# Others.net
KiCad netlist of a schematic drawn in Altium Designer
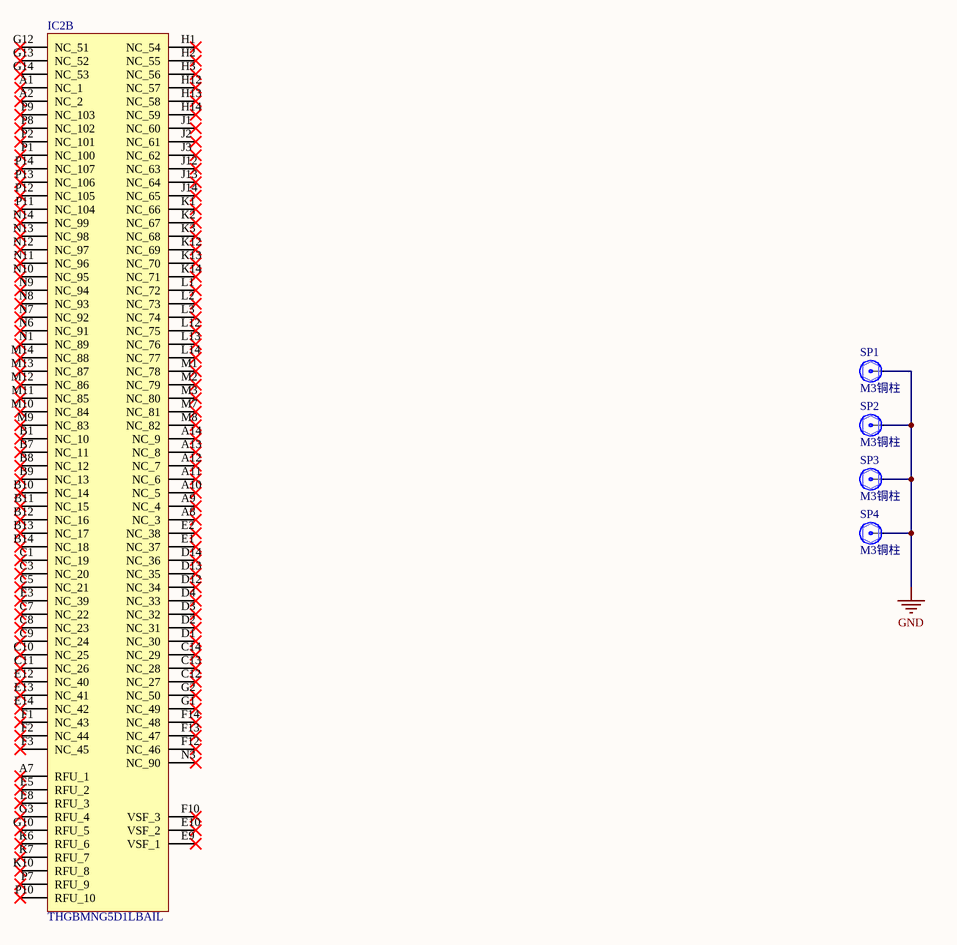
[diagram p0: Others.SchDoc]

(export (version "E")
  (design (tool "Eeschema 10.0.6"))
  (components
    (comp (ref "IC2")
      (value "THGBMNG5D1LBAIL")
      (footprint "SamacSys:BGA153C50P14X14_1150X1300X80")
      (description "Integrated Circuit")
      (libsource (lib "SamacSys") (part "THGBMNG5D1LBAIL"))
    )
    (comp (ref "SP1")
      (value "M3铜柱")
      (footprint "M3x4+6_L")
      (description "铜柱")
      (libsource (lib "0.5 - 按键_开关_蜂鸣器_电池_测试点_Mark点_铜柱") (part "铜柱加头小焊盘"))
    )
    (comp (ref "SP2")
      (value "M3铜柱")
      (footprint "M3x4+6_L")
      (description "铜柱")
      (libsource (lib "0.5 - 按键_开关_蜂鸣器_电池_测试点_Mark点_铜柱") (part "铜柱加头小焊盘"))
    )
    (comp (ref "SP3")
      (value "M3铜柱")
      (footprint "M3x4+6_L")
      (description "铜柱")
      (libsource (lib "0.5 - 按键_开关_蜂鸣器_电池_测试点_Mark点_铜柱") (part "铜柱加头小焊盘"))
    )
    (comp (ref "SP4")
      (value "M3铜柱")
      (footprint "M3x4+6_L")
      (description "铜柱")
      (libsource (lib "0.5 - 按键_开关_蜂鸣器_电池_测试点_Mark点_铜柱") (part "铜柱加头小焊盘"))
    )
  )
  (nets
    (net (code "1") (name "GND") (class "Default")
      (node (ref "SP1") (pin "1") (pinfunction "1_1") (pintype "passive"))
      (node (ref "SP2") (pin "1") (pinfunction "1_1") (pintype "passive"))
      (node (ref "SP3") (pin "1") (pinfunction "1_1") (pintype "passive"))
      (node (ref "SP4") (pin "1") (pinfunction "1_1") (pintype "passive"))
    )
    (net (code "2") (name "unconnected-(IC2B-NC_1-PadA1)") (class "Default")
      (node (ref "IC2") (pin "A1") (pinfunction "NC_1_A1") (pintype "passive+no_connect"))
    )
    (net (code "3") (name "unconnected-(IC2B-NC_2-PadA2)") (class "Default")
      (node (ref "IC2") (pin "A2") (pinfunction "NC_2_A2") (pintype "passive+no_connect"))
    )
    (net (code "4") (name "unconnected-(IC2B-NC_3-PadA8)") (class "Default")
      (node (ref "IC2") (pin "A8") (pinfunction "NC_3_A8") (pintype "passive+no_connect"))
    )
    (net (code "5") (name "unconnected-(IC2B-NC_4-PadA9)") (class "Default")
      (node (ref "IC2") (pin "A9") (pinfunction "NC_4_A9") (pintype "passive+no_connect"))
    )
    (net (code "6") (name "unconnected-(IC2B-NC_5-PadA10)") (class "Default")
      (node (ref "IC2") (pin "A10") (pinfunction "NC_5_A10") (pintype "passive+no_connect"))
    )
    (net (code "7") (name "unconnected-(IC2B-NC_6-PadA11)") (class "Default")
      (node (ref "IC2") (pin "A11") (pinfunction "NC_6_A11") (pintype "passive+no_connect"))
    )
    (net (code "8") (name "unconnected-(IC2B-NC_7-PadA12)") (class "Default")
      (node (ref "IC2") (pin "A12") (pinfunction "NC_7_A12") (pintype "passive+no_connect"))
    )
    (net (code "9") (name "unconnected-(IC2B-NC_8-PadA13)") (class "Default")
      (node (ref "IC2") (pin "A13") (pinfunction "NC_8_A13") (pintype "passive+no_connect"))
    )
    (net (code "10") (name "unconnected-(IC2B-NC_9-PadA14)") (class "Default")
      (node (ref "IC2") (pin "A14") (pinfunction "NC_9_A14") (pintype "passive+no_connect"))
    )
    (net (code "11") (name "unconnected-(IC2B-NC_10-PadB1)") (class "Default")
      (node (ref "IC2") (pin "B1") (pinfunction "NC_10_B1") (pintype "passive+no_connect"))
    )
    (net (code "12") (name "unconnected-(IC2B-NC_11-PadB7)") (class "Default")
      (node (ref "IC2") (pin "B7") (pinfunction "NC_11_B7") (pintype "passive+no_connect"))
    )
    (net (code "13") (name "unconnected-(IC2B-NC_12-PadB8)") (class "Default")
      (node (ref "IC2") (pin "B8") (pinfunction "NC_12_B8") (pintype "passive+no_connect"))
    )
    (net (code "14") (name "unconnected-(IC2B-NC_13-PadB9)") (class "Default")
      (node (ref "IC2") (pin "B9") (pinfunction "NC_13_B9") (pintype "passive+no_connect"))
    )
    (net (code "15") (name "unconnected-(IC2B-NC_14-PadB10)") (class "Default")
      (node (ref "IC2") (pin "B10") (pinfunction "NC_14_B10") (pintype "passive+no_connect"))
    )
    (net (code "16") (name "unconnected-(IC2B-NC_15-PadB11)") (class "Default")
      (node (ref "IC2") (pin "B11") (pinfunction "NC_15_B11") (pintype "passive+no_connect"))
    )
    (net (code "17") (name "unconnected-(IC2B-NC_16-PadB12)") (class "Default")
      (node (ref "IC2") (pin "B12") (pinfunction "NC_16_B12") (pintype "passive+no_connect"))
    )
    (net (code "18") (name "unconnected-(IC2B-NC_17-PadB13)") (class "Default")
      (node (ref "IC2") (pin "B13") (pinfunction "NC_17_B13") (pintype "passive+no_connect"))
    )
    (net (code "19") (name "unconnected-(IC2B-NC_18-PadB14)") (class "Default")
      (node (ref "IC2") (pin "B14") (pinfunction "NC_18_B14") (pintype "passive+no_connect"))
    )
    (net (code "20") (name "unconnected-(IC2B-NC_19-PadC1)") (class "Default")
      (node (ref "IC2") (pin "C1") (pinfunction "NC_19_C1") (pintype "passive+no_connect"))
    )
    (net (code "21") (name "unconnected-(IC2B-NC_20-PadC3)") (class "Default")
      (node (ref "IC2") (pin "C3") (pinfunction "NC_20_C3") (pintype "passive+no_connect"))
    )
    (net (code "22") (name "unconnected-(IC2B-NC_21-PadC5)") (class "Default")
      (node (ref "IC2") (pin "C5") (pinfunction "NC_21_C5") (pintype "passive+no_connect"))
    )
    (net (code "23") (name "unconnected-(IC2B-NC_22-PadC7)") (class "Default")
      (node (ref "IC2") (pin "C7") (pinfunction "NC_22_C7") (pintype "passive+no_connect"))
    )
    (net (code "24") (name "unconnected-(IC2B-NC_23-PadC8)") (class "Default")
      (node (ref "IC2") (pin "C8") (pinfunction "NC_23_C8") (pintype "passive+no_connect"))
    )
    (net (code "25") (name "unconnected-(IC2B-NC_24-PadC9)") (class "Default")
      (node (ref "IC2") (pin "C9") (pinfunction "NC_24_C9") (pintype "passive+no_connect"))
    )
    (net (code "26") (name "unconnected-(IC2B-NC_25-PadC10)") (class "Default")
      (node (ref "IC2") (pin "C10") (pinfunction "NC_25_C10") (pintype "passive+no_connect"))
    )
    (net (code "27") (name "unconnected-(IC2B-NC_26-PadC11)") (class "Default")
      (node (ref "IC2") (pin "C11") (pinfunction "NC_26_C11") (pintype "passive+no_connect"))
    )
    (net (code "28") (name "unconnected-(IC2B-NC_27-PadC12)") (class "Default")
      (node (ref "IC2") (pin "C12") (pinfunction "NC_27_C12") (pintype "passive+no_connect"))
    )
    (net (code "29") (name "unconnected-(IC2B-NC_28-PadC13)") (class "Default")
      (node (ref "IC2") (pin "C13") (pinfunction "NC_28_C13") (pintype "passive+no_connect"))
    )
    (net (code "30") (name "unconnected-(IC2B-NC_29-PadC14)") (class "Default")
      (node (ref "IC2") (pin "C14") (pinfunction "NC_29_C14") (pintype "passive+no_connect"))
    )
    (net (code "31") (name "unconnected-(IC2B-NC_30-PadD1)") (class "Default")
      (node (ref "IC2") (pin "D1") (pinfunction "NC_30_D1") (pintype "passive+no_connect"))
    )
    (net (code "32") (name "unconnected-(IC2B-NC_31-PadD2)") (class "Default")
      (node (ref "IC2") (pin "D2") (pinfunction "NC_31_D2") (pintype "passive+no_connect"))
    )
    (net (code "33") (name "unconnected-(IC2B-NC_32-PadD3)") (class "Default")
      (node (ref "IC2") (pin "D3") (pinfunction "NC_32_D3") (pintype "passive+no_connect"))
    )
    (net (code "34") (name "unconnected-(IC2B-NC_33-PadD4)") (class "Default")
      (node (ref "IC2") (pin "D4") (pinfunction "NC_33_D4") (pintype "passive+no_connect"))
    )
    (net (code "35") (name "unconnected-(IC2B-NC_34-PadD12)") (class "Default")
      (node (ref "IC2") (pin "D12") (pinfunction "NC_34_D12") (pintype "passive+no_connect"))
    )
    (net (code "36") (name "unconnected-(IC2B-NC_35-PadD13)") (class "Default")
      (node (ref "IC2") (pin "D13") (pinfunction "NC_35_D13") (pintype "passive+no_connect"))
    )
    (net (code "37") (name "unconnected-(IC2B-NC_36-PadD14)") (class "Default")
      (node (ref "IC2") (pin "D14") (pinfunction "NC_36_D14") (pintype "passive+no_connect"))
    )
    (net (code "38") (name "unconnected-(IC2B-NC_37-PadE1)") (class "Default")
      (node (ref "IC2") (pin "E1") (pinfunction "NC_37_E1") (pintype "passive+no_connect"))
    )
    (net (code "39") (name "unconnected-(IC2B-NC_38-PadE2)") (class "Default")
      (node (ref "IC2") (pin "E2") (pinfunction "NC_38_E2") (pintype "passive+no_connect"))
    )
    (net (code "40") (name "unconnected-(IC2B-NC_39-PadE3)") (class "Default")
      (node (ref "IC2") (pin "E3") (pinfunction "NC_39_E3") (pintype "passive+no_connect"))
    )
    (net (code "41") (name "unconnected-(IC2B-NC_40-PadE12)") (class "Default")
      (node (ref "IC2") (pin "E12") (pinfunction "NC_40_E12") (pintype "passive+no_connect"))
    )
    (net (code "42") (name "unconnected-(IC2B-NC_41-PadE13)") (class "Default")
      (node (ref "IC2") (pin "E13") (pinfunction "NC_41_E13") (pintype "passive+no_connect"))
    )
    (net (code "43") (name "unconnected-(IC2B-NC_42-PadE14)") (class "Default")
      (node (ref "IC2") (pin "E14") (pinfunction "NC_42_E14") (pintype "passive+no_connect"))
    )
    (net (code "44") (name "unconnected-(IC2B-NC_43-PadF1)") (class "Default")
      (node (ref "IC2") (pin "F1") (pinfunction "NC_43_F1") (pintype "passive+no_connect"))
    )
    (net (code "45") (name "unconnected-(IC2B-NC_44-PadF2)") (class "Default")
      (node (ref "IC2") (pin "F2") (pinfunction "NC_44_F2") (pintype "passive+no_connect"))
    )
    (net (code "46") (name "unconnected-(IC2B-NC_45-PadF3)") (class "Default")
      (node (ref "IC2") (pin "F3") (pinfunction "NC_45_F3") (pintype "passive+no_connect"))
    )
    (net (code "47") (name "unconnected-(IC2B-NC_46-PadF12)") (class "Default")
      (node (ref "IC2") (pin "F12") (pinfunction "NC_46_F12") (pintype "passive+no_connect"))
    )
    (net (code "48") (name "unconnected-(IC2B-NC_47-PadF13)") (class "Default")
      (node (ref "IC2") (pin "F13") (pinfunction "NC_47_F13") (pintype "passive+no_connect"))
    )
    (net (code "49") (name "unconnected-(IC2B-NC_48-PadF14)") (class "Default")
      (node (ref "IC2") (pin "F14") (pinfunction "NC_48_F14") (pintype "passive+no_connect"))
    )
    (net (code "50") (name "unconnected-(IC2B-NC_49-PadG1)") (class "Default")
      (node (ref "IC2") (pin "G1") (pinfunction "NC_49_G1") (pintype "passive+no_connect"))
    )
    (net (code "51") (name "unconnected-(IC2B-NC_50-PadG2)") (class "Default")
      (node (ref "IC2") (pin "G2") (pinfunction "NC_50_G2") (pintype "passive+no_connect"))
    )
    (net (code "52") (name "unconnected-(IC2B-NC_51-PadG12)") (class "Default")
      (node (ref "IC2") (pin "G12") (pinfunction "NC_51_G12") (pintype "passive+no_connect"))
    )
    (net (code "53") (name "unconnected-(IC2B-NC_52-PadG13)") (class "Default")
      (node (ref "IC2") (pin "G13") (pinfunction "NC_52_G13") (pintype "passive+no_connect"))
    )
    (net (code "54") (name "unconnected-(IC2B-NC_53-PadG14)") (class "Default")
      (node (ref "IC2") (pin "G14") (pinfunction "NC_53_G14") (pintype "passive+no_connect"))
    )
    (net (code "55") (name "unconnected-(IC2B-NC_54-PadH1)") (class "Default")
      (node (ref "IC2") (pin "H1") (pinfunction "NC_54_H1") (pintype "passive+no_connect"))
    )
    (net (code "56") (name "unconnected-(IC2B-NC_55-PadH2)") (class "Default")
      (node (ref "IC2") (pin "H2") (pinfunction "NC_55_H2") (pintype "passive+no_connect"))
    )
    (net (code "57") (name "unconnected-(IC2B-NC_56-PadH3)") (class "Default")
      (node (ref "IC2") (pin "H3") (pinfunction "NC_56_H3") (pintype "passive+no_connect"))
    )
    (net (code "58") (name "unconnected-(IC2B-NC_57-PadH12)") (class "Default")
      (node (ref "IC2") (pin "H12") (pinfunction "NC_57_H12") (pintype "passive+no_connect"))
    )
    (net (code "59") (name "unconnected-(IC2B-NC_58-PadH13)") (class "Default")
      (node (ref "IC2") (pin "H13") (pinfunction "NC_58_H13") (pintype "passive+no_connect"))
    )
    (net (code "60") (name "unconnected-(IC2B-NC_59-PadH14)") (class "Default")
      (node (ref "IC2") (pin "H14") (pinfunction "NC_59_H14") (pintype "passive+no_connect"))
    )
    (net (code "61") (name "unconnected-(IC2B-NC_60-PadJ1)") (class "Default")
      (node (ref "IC2") (pin "J1") (pinfunction "NC_60_J1") (pintype "passive+no_connect"))
    )
    (net (code "62") (name "unconnected-(IC2B-NC_61-PadJ2)") (class "Default")
      (node (ref "IC2") (pin "J2") (pinfunction "NC_61_J2") (pintype "passive+no_connect"))
    )
    (net (code "63") (name "unconnected-(IC2B-NC_62-PadJ3)") (class "Default")
      (node (ref "IC2") (pin "J3") (pinfunction "NC_62_J3") (pintype "passive+no_connect"))
    )
    (net (code "64") (name "unconnected-(IC2B-NC_63-PadJ12)") (class "Default")
      (node (ref "IC2") (pin "J12") (pinfunction "NC_63_J12") (pintype "passive+no_connect"))
    )
    (net (code "65") (name "unconnected-(IC2B-NC_64-PadJ13)") (class "Default")
      (node (ref "IC2") (pin "J13") (pinfunction "NC_64_J13") (pintype "passive+no_connect"))
    )
    (net (code "66") (name "unconnected-(IC2B-NC_65-PadJ14)") (class "Default")
      (node (ref "IC2") (pin "J14") (pinfunction "NC_65_J14") (pintype "passive+no_connect"))
    )
    (net (code "67") (name "unconnected-(IC2B-NC_66-PadK1)") (class "Default")
      (node (ref "IC2") (pin "K1") (pinfunction "NC_66_K1") (pintype "passive+no_connect"))
    )
    (net (code "68") (name "unconnected-(IC2B-NC_67-PadK2)") (class "Default")
      (node (ref "IC2") (pin "K2") (pinfunction "NC_67_K2") (pintype "passive+no_connect"))
    )
    (net (code "69") (name "unconnected-(IC2B-NC_68-PadK3)") (class "Default")
      (node (ref "IC2") (pin "K3") (pinfunction "NC_68_K3") (pintype "passive+no_connect"))
    )
    (net (code "70") (name "unconnected-(IC2B-NC_69-PadK12)") (class "Default")
      (node (ref "IC2") (pin "K12") (pinfunction "NC_69_K12") (pintype "passive+no_connect"))
    )
    (net (code "71") (name "unconnected-(IC2B-NC_70-PadK13)") (class "Default")
      (node (ref "IC2") (pin "K13") (pinfunction "NC_70_K13") (pintype "passive+no_connect"))
    )
    (net (code "72") (name "unconnected-(IC2B-NC_71-PadK14)") (class "Default")
      (node (ref "IC2") (pin "K14") (pinfunction "NC_71_K14") (pintype "passive+no_connect"))
    )
    (net (code "73") (name "unconnected-(IC2B-NC_72-PadL1)") (class "Default")
      (node (ref "IC2") (pin "L1") (pinfunction "NC_72_L1") (pintype "passive+no_connect"))
    )
    (net (code "74") (name "unconnected-(IC2B-NC_73-PadL2)") (class "Default")
      (node (ref "IC2") (pin "L2") (pinfunction "NC_73_L2") (pintype "passive+no_connect"))
    )
    (net (code "75") (name "unconnected-(IC2B-NC_74-PadL3)") (class "Default")
      (node (ref "IC2") (pin "L3") (pinfunction "NC_74_L3") (pintype "passive+no_connect"))
    )
    (net (code "76") (name "unconnected-(IC2B-NC_75-PadL12)") (class "Default")
      (node (ref "IC2") (pin "L12") (pinfunction "NC_75_L12") (pintype "passive+no_connect"))
    )
    (net (code "77") (name "unconnected-(IC2B-NC_76-PadL13)") (class "Default")
      (node (ref "IC2") (pin "L13") (pinfunction "NC_76_L13") (pintype "passive+no_connect"))
    )
    (net (code "78") (name "unconnected-(IC2B-NC_77-PadL14)") (class "Default")
      (node (ref "IC2") (pin "L14") (pinfunction "NC_77_L14") (pintype "passive+no_connect"))
    )
    (net (code "79") (name "unconnected-(IC2B-NC_78-PadM1)") (class "Default")
      (node (ref "IC2") (pin "M1") (pinfunction "NC_78_M1") (pintype "passive+no_connect"))
    )
    (net (code "80") (name "unconnected-(IC2B-NC_79-PadM2)") (class "Default")
      (node (ref "IC2") (pin "M2") (pinfunction "NC_79_M2") (pintype "passive+no_connect"))
    )
    (net (code "81") (name "unconnected-(IC2B-NC_80-PadM3)") (class "Default")
      (node (ref "IC2") (pin "M3") (pinfunction "NC_80_M3") (pintype "passive+no_connect"))
    )
    (net (code "82") (name "unconnected-(IC2B-NC_81-PadM7)") (class "Default")
      (node (ref "IC2") (pin "M7") (pinfunction "NC_81_M7") (pintype "passive+no_connect"))
    )
    (net (code "83") (name "unconnected-(IC2B-NC_82-PadM8)") (class "Default")
      (node (ref "IC2") (pin "M8") (pinfunction "NC_82_M8") (pintype "passive+no_connect"))
    )
    (net (code "84") (name "unconnected-(IC2B-NC_83-PadM9)") (class "Default")
      (node (ref "IC2") (pin "M9") (pinfunction "NC_83_M9") (pintype "passive+no_connect"))
    )
    (net (code "85") (name "unconnected-(IC2B-NC_84-PadM10)") (class "Default")
      (node (ref "IC2") (pin "M10") (pinfunction "NC_84_M10") (pintype "passive+no_connect"))
    )
    (net (code "86") (name "unconnected-(IC2B-NC_85-PadM11)") (class "Default")
      (node (ref "IC2") (pin "M11") (pinfunction "NC_85_M11") (pintype "passive+no_connect"))
    )
    (net (code "87") (name "unconnected-(IC2B-NC_86-PadM12)") (class "Default")
      (node (ref "IC2") (pin "M12") (pinfunction "NC_86_M12") (pintype "passive+no_connect"))
    )
    (net (code "88") (name "unconnected-(IC2B-NC_87-PadM13)") (class "Default")
      (node (ref "IC2") (pin "M13") (pinfunction "NC_87_M13") (pintype "passive+no_connect"))
    )
    (net (code "89") (name "unconnected-(IC2B-NC_88-PadM14)") (class "Default")
      (node (ref "IC2") (pin "M14") (pinfunction "NC_88_M14") (pintype "passive+no_connect"))
    )
    (net (code "90") (name "unconnected-(IC2B-NC_89-PadN1)") (class "Default")
      (node (ref "IC2") (pin "N1") (pinfunction "NC_89_N1") (pintype "passive+no_connect"))
    )
    (net (code "91") (name "unconnected-(IC2B-NC_90-PadN3)") (class "Default")
      (node (ref "IC2") (pin "N3") (pinfunction "NC_90_N3") (pintype "passive+no_connect"))
    )
    (net (code "92") (name "unconnected-(IC2B-NC_91-PadN6)") (class "Default")
      (node (ref "IC2") (pin "N6") (pinfunction "NC_91_N6") (pintype "passive+no_connect"))
    )
    (net (code "93") (name "unconnected-(IC2B-NC_92-PadN7)") (class "Default")
      (node (ref "IC2") (pin "N7") (pinfunction "NC_92_N7") (pintype "passive+no_connect"))
    )
    (net (code "94") (name "unconnected-(IC2B-NC_93-PadN8)") (class "Default")
      (node (ref "IC2") (pin "N8") (pinfunction "NC_93_N8") (pintype "passive+no_connect"))
    )
    (net (code "95") (name "unconnected-(IC2B-NC_94-PadN9)") (class "Default")
      (node (ref "IC2") (pin "N9") (pinfunction "NC_94_N9") (pintype "passive+no_connect"))
    )
    (net (code "96") (name "unconnected-(IC2B-NC_95-PadN10)") (class "Default")
      (node (ref "IC2") (pin "N10") (pinfunction "NC_95_N10") (pintype "passive+no_connect"))
    )
    (net (code "97") (name "unconnected-(IC2B-NC_96-PadN11)") (class "Default")
      (node (ref "IC2") (pin "N11") (pinfunction "NC_96_N11") (pintype "passive+no_connect"))
    )
    (net (code "98") (name "unconnected-(IC2B-NC_97-PadN12)") (class "Default")
      (node (ref "IC2") (pin "N12") (pinfunction "NC_97_N12") (pintype "passive+no_connect"))
    )
    (net (code "99") (name "unconnected-(IC2B-NC_98-PadN13)") (class "Default")
      (node (ref "IC2") (pin "N13") (pinfunction "NC_98_N13") (pintype "passive+no_connect"))
    )
    (net (code "100") (name "unconnected-(IC2B-NC_99-PadN14)") (class "Default")
      (node (ref "IC2") (pin "N14") (pinfunction "NC_99_N14") (pintype "passive+no_connect"))
    )
    (net (code "101") (name "unconnected-(IC2B-NC_100-PadP1)") (class "Default")
      (node (ref "IC2") (pin "P1") (pinfunction "NC_100_P1") (pintype "passive+no_connect"))
    )
    (net (code "102") (name "unconnected-(IC2B-NC_101-PadP2)") (class "Default")
      (node (ref "IC2") (pin "P2") (pinfunction "NC_101_P2") (pintype "passive+no_connect"))
    )
    (net (code "103") (name "unconnected-(IC2B-NC_102-PadP8)") (class "Default")
      (node (ref "IC2") (pin "P8") (pinfunction "NC_102_P8") (pintype "passive+no_connect"))
    )
    (net (code "104") (name "unconnected-(IC2B-NC_103-PadP9)") (class "Default")
      (node (ref "IC2") (pin "P9") (pinfunction "NC_103_P9") (pintype "passive+no_connect"))
    )
    (net (code "105") (name "unconnected-(IC2B-NC_104-PadP11)") (class "Default")
      (node (ref "IC2") (pin "P11") (pinfunction "NC_104_P11") (pintype "passive+no_connect"))
    )
    (net (code "106") (name "unconnected-(IC2B-NC_105-PadP12)") (class "Default")
      (node (ref "IC2") (pin "P12") (pinfunction "NC_105_P12") (pintype "passive+no_connect"))
    )
    (net (code "107") (name "unconnected-(IC2B-NC_106-PadP13)") (class "Default")
      (node (ref "IC2") (pin "P13") (pinfunction "NC_106_P13") (pintype "passive+no_connect"))
    )
    (net (code "108") (name "unconnected-(IC2B-NC_107-PadP14)") (class "Default")
      (node (ref "IC2") (pin "P14") (pinfunction "NC_107_P14") (pintype "passive+no_connect"))
    )
    (net (code "109") (name "unconnected-(IC2B-RFU_1-PadA7)") (class "Default")
      (node (ref "IC2") (pin "A7") (pinfunction "RFU_1_A7") (pintype "passive+no_connect"))
    )
    (net (code "110") (name "unconnected-(IC2B-RFU_2-PadE5)") (class "Default")
      (node (ref "IC2") (pin "E5") (pinfunction "RFU_2_E5") (pintype "passive+no_connect"))
    )
    (net (code "111") (name "unconnected-(IC2B-RFU_3-PadE8)") (class "Default")
      (node (ref "IC2") (pin "E8") (pinfunction "RFU_3_E8") (pintype "passive+no_connect"))
    )
    (net (code "112") (name "unconnected-(IC2B-RFU_4-PadG3)") (class "Default")
      (node (ref "IC2") (pin "G3") (pinfunction "RFU_4_G3") (pintype "passive+no_connect"))
    )
    (net (code "113") (name "unconnected-(IC2B-RFU_5-PadG10)") (class "Default")
      (node (ref "IC2") (pin "G10") (pinfunction "RFU_5_G10") (pintype "passive+no_connect"))
    )
    (net (code "114") (name "unconnected-(IC2B-RFU_6-PadK6)") (class "Default")
      (node (ref "IC2") (pin "K6") (pinfunction "RFU_6_K6") (pintype "passive+no_connect"))
    )
    (net (code "115") (name "unconnected-(IC2B-RFU_7-PadK7)") (class "Default")
      (node (ref "IC2") (pin "K7") (pinfunction "RFU_7_K7") (pintype "passive+no_connect"))
    )
    (net (code "116") (name "unconnected-(IC2B-RFU_8-PadK10)") (class "Default")
      (node (ref "IC2") (pin "K10") (pinfunction "RFU_8_K10") (pintype "passive+no_connect"))
    )
    (net (code "117") (name "unconnected-(IC2B-RFU_9-PadP7)") (class "Default")
      (node (ref "IC2") (pin "P7") (pinfunction "RFU_9_P7") (pintype "passive+no_connect"))
    )
    (net (code "118") (name "unconnected-(IC2B-RFU_10-PadP10)") (class "Default")
      (node (ref "IC2") (pin "P10") (pinfunction "RFU_10_P10") (pintype "passive+no_connect"))
    )
    (net (code "119") (name "unconnected-(IC2B-VSF_1-PadE9)") (class "Default")
      (node (ref "IC2") (pin "E9") (pinfunction "VSF_1_E9") (pintype "passive+no_connect"))
    )
    (net (code "120") (name "unconnected-(IC2B-VSF_2-PadE10)") (class "Default")
      (node (ref "IC2") (pin "E10") (pinfunction "VSF_2_E10") (pintype "passive+no_connect"))
    )
    (net (code "121") (name "unconnected-(IC2B-VSF_3-PadF10)") (class "Default")
      (node (ref "IC2") (pin "F10") (pinfunction "VSF_3_F10") (pintype "passive+no_connect"))
    )
  )
)
